# InterfacesA_USBFTDI.net
KiCad netlist of a schematic drawn in Altium Designer
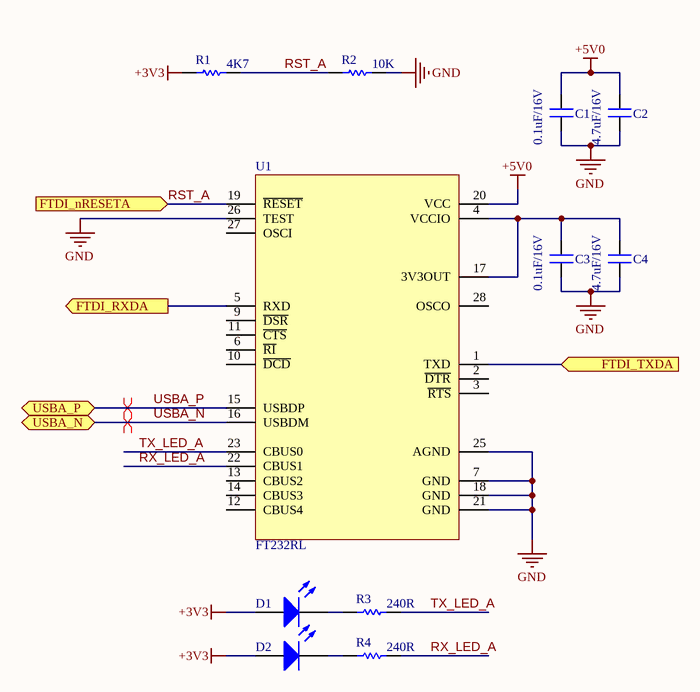
[diagram p0: InterfacesA_USBFTDI.SchDoc]

(export (version "E")
  (design (tool "Eeschema 10.0.6"))
  (components
    (comp (ref "C1")
      (value "0.1uF/16V")
      (footprint "CAP_0805")
      (fields (field (name "Comment") "CAP_0805"))
      (libsource (lib "AdapterLib") (part "CAP_0805"))
    )
    (comp (ref "C2")
      (value "4.7uF/16V")
      (footprint "CAP_0805")
      (fields (field (name "Comment") "CAP_0805"))
      (libsource (lib "AdapterLib") (part "CAP_0805"))
    )
    (comp (ref "C3")
      (value "0.1uF/16V")
      (footprint "CAP_0805")
      (fields (field (name "Comment") "CAP_0805"))
      (libsource (lib "AdapterLib") (part "CAP_0805"))
    )
    (comp (ref "C4")
      (value "4.7uF/16V")
      (footprint "CAP_0805")
      (fields (field (name "Comment") "CAP_0805"))
      (libsource (lib "AdapterLib") (part "CAP_0805"))
    )
    (comp (ref "D1")
      (value "LED_0603")
      (footprint "LED_0603")
      (libsource (lib "AdapterLib") (part "LED_0603"))
    )
    (comp (ref "D2")
      (value "LED_0603")
      (footprint "LED_0603")
      (libsource (lib "AdapterLib") (part "LED_0603"))
    )
    (comp (ref "R1")
      (value "4K7")
      (footprint "RES_0805")
      (fields (field (name "Comment") "RES_0805"))
      (libsource (lib "AdapterLib") (part "RES_0805"))
    )
    (comp (ref "R2")
      (value "10K")
      (footprint "RES_0805")
      (fields (field (name "Comment") "RES_0805"))
      (libsource (lib "AdapterLib") (part "RES_0805"))
    )
    (comp (ref "R3")
      (value "240R")
      (footprint "RES_0805")
      (fields (field (name "Comment") "RES_0805"))
      (libsource (lib "AdapterLib") (part "RES_0805"))
    )
    (comp (ref "R4")
      (value "240R")
      (footprint "RES_0805")
      (fields (field (name "Comment") "RES_0805"))
      (libsource (lib "AdapterLib") (part "RES_0805"))
    )
    (comp (ref "U1")
      (value "FT232RL")
      (footprint "AdapterLib:FT232RL")
      (description "USB Bridge, USB to UART USB 2.0 UART Interface 28-SSOP")
      (fields (field (name "DIGI-KEY_PART_NUMBER") "768-1007-1-ND") (field (name "MP") "FT232RL-REEL"))
      (libsource (lib "AdapterLib") (part "FT232RL"))
    )
  )
  (nets
    (net (code "1") (name "+3V3") (class "Default")
      (node (ref "D1") (pin "1") (pinfunction "A_1") (pintype "passive"))
      (node (ref "D2") (pin "1") (pinfunction "A_1") (pintype "passive"))
      (node (ref "R1") (pin "1") (pinfunction "1_1") (pintype "passive"))
    )
    (net (code "2") (name "+5V0") (class "Default")
      (node (ref "C1") (pin "1") (pinfunction "1_1") (pintype "passive"))
      (node (ref "C2") (pin "2") (pinfunction "2_2") (pintype "passive"))
      (node (ref "U1") (pin "20") (pinfunction "VCC_20") (pintype "passive"))
    )
    (net (code "3") (name "/FTDI_RXDA") (class "Default")
      (node (ref "U1") (pin "5") (pinfunction "RXD_5") (pintype "passive"))
    )
    (net (code "4") (name "/FTDI_TXDA") (class "Default")
      (node (ref "U1") (pin "1") (pinfunction "TXD_1") (pintype "passive"))
    )
    (net (code "5") (name "/RST_A") (class "Default")
      (node (ref "R1") (pin "2") (pinfunction "2_2") (pintype "passive"))
      (node (ref "R2") (pin "1") (pinfunction "1_1") (pintype "passive"))
      (node (ref "U1") (pin "19") (pinfunction "~{RESET}_19") (pintype "passive"))
    )
    (net (code "6") (name "/RX_LED_A") (class "Default")
      (node (ref "R4") (pin "2") (pinfunction "2_2") (pintype "passive"))
      (node (ref "U1") (pin "22") (pinfunction "CBUS1_22") (pintype "passive"))
    )
    (net (code "7") (name "/TX_LED_A") (class "Default")
      (node (ref "R3") (pin "2") (pinfunction "2_2") (pintype "passive"))
      (node (ref "U1") (pin "23") (pinfunction "CBUS0_23") (pintype "passive"))
    )
    (net (code "8") (name "/USBA_N") (class "Default")
      (node (ref "U1") (pin "16") (pinfunction "USBDM_16") (pintype "passive"))
    )
    (net (code "9") (name "/USBA_P") (class "Default")
      (node (ref "U1") (pin "15") (pinfunction "USBDP_15") (pintype "passive"))
    )
    (net (code "10") (name "GND") (class "Default")
      (node (ref "C1") (pin "2") (pinfunction "2_2") (pintype "passive"))
      (node (ref "C2") (pin "1") (pinfunction "1_1") (pintype "passive"))
      (node (ref "C3") (pin "2") (pinfunction "2_2") (pintype "passive"))
      (node (ref "C4") (pin "1") (pinfunction "1_1") (pintype "passive"))
      (node (ref "R2") (pin "2") (pinfunction "2_2") (pintype "passive"))
      (node (ref "U1") (pin "18") (pinfunction "GND_18") (pintype "passive"))
      (node (ref "U1") (pin "21") (pinfunction "GND_21") (pintype "passive"))
      (node (ref "U1") (pin "25") (pinfunction "AGND_25") (pintype "passive"))
      (node (ref "U1") (pin "26") (pinfunction "TEST_26") (pintype "passive"))
      (node (ref "U1") (pin "7") (pinfunction "GND_7") (pintype "passive"))
    )
    (net (code "11") (name "Net-(D1-K)") (class "Default")
      (node (ref "D1") (pin "2") (pinfunction "K_2") (pintype "passive"))
      (node (ref "R3") (pin "1") (pinfunction "1_1") (pintype "passive"))
    )
    (net (code "12") (name "Net-(D2-K)") (class "Default")
      (node (ref "D2") (pin "2") (pinfunction "K_2") (pintype "passive"))
      (node (ref "R4") (pin "1") (pinfunction "1_1") (pintype "passive"))
    )
    (net (code "13") (name "Net-(U1-3V3OUT)") (class "Default")
      (node (ref "C3") (pin "1") (pinfunction "1_1") (pintype "passive"))
      (node (ref "C4") (pin "2") (pinfunction "2_2") (pintype "passive"))
      (node (ref "U1") (pin "17") (pinfunction "3V3OUT_17") (pintype "passive"))
      (node (ref "U1") (pin "4") (pinfunction "VCCIO_4") (pintype "passive"))
    )
    (net (code "14") (name "unconnected-(U1-CBUS2-Pad13)") (class "Default")
      (node (ref "U1") (pin "13") (pinfunction "CBUS2_13") (pintype "passive"))
    )
    (net (code "15") (name "unconnected-(U1-CBUS3-Pad14)") (class "Default")
      (node (ref "U1") (pin "14") (pinfunction "CBUS3_14") (pintype "passive"))
    )
    (net (code "16") (name "unconnected-(U1-CBUS4-Pad12)") (class "Default")
      (node (ref "U1") (pin "12") (pinfunction "CBUS4_12") (pintype "passive"))
    )
    (net (code "17") (name "unconnected-(U1-OSCI-Pad27)") (class "Default")
      (node (ref "U1") (pin "27") (pinfunction "OSCI_27") (pintype "passive"))
    )
    (net (code "18") (name "unconnected-(U1-OSCO-Pad28)") (class "Default")
      (node (ref "U1") (pin "28") (pinfunction "OSCO_28") (pintype "passive"))
    )
    (net (code "19") (name "unconnected-(U1-~{CTS}-Pad11)") (class "Default")
      (node (ref "U1") (pin "11") (pinfunction "~{CTS}_11") (pintype "passive"))
    )
    (net (code "20") (name "unconnected-(U1-~{DCD}-Pad10)") (class "Default")
      (node (ref "U1") (pin "10") (pinfunction "~{DCD}_10") (pintype "passive"))
    )
    (net (code "21") (name "unconnected-(U1-~{DSR}-Pad9)") (class "Default")
      (node (ref "U1") (pin "9") (pinfunction "~{DSR}_9") (pintype "passive"))
    )
    (net (code "22") (name "unconnected-(U1-~{DTR}-Pad2)") (class "Default")
      (node (ref "U1") (pin "2") (pinfunction "~{DTR}_2") (pintype "passive"))
    )
    (net (code "23") (name "unconnected-(U1-~{RI}-Pad6)") (class "Default")
      (node (ref "U1") (pin "6") (pinfunction "~{RI}_6") (pintype "passive"))
    )
    (net (code "24") (name "unconnected-(U1-~{RTS}-Pad3)") (class "Default")
      (node (ref "U1") (pin "3") (pinfunction "~{RTS}_3") (pintype "passive"))
    )
  )
)
